# ui.net
KiCad netlist of a schematic drawn in Altium Designer
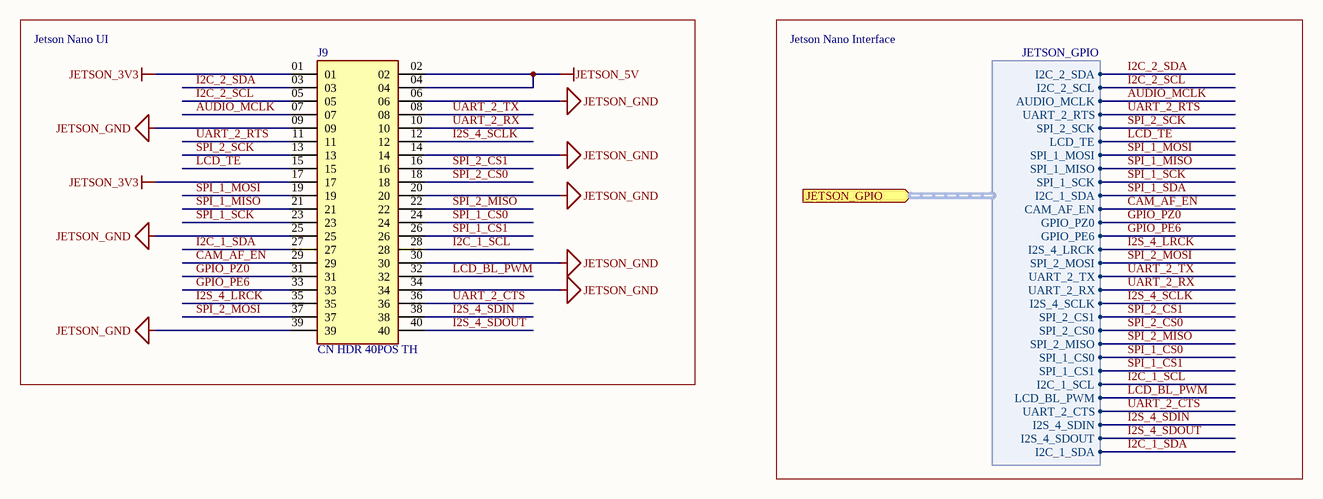
[diagram p0: ui.SchDoc]

(export (version "E")
  (design (tool "Eeschema 10.0.6"))
  (components
    (comp (ref "J9")
      (value "CN HDR 40POS TH")
      (footprint "SAMTEC_SSQ-120-22-G-D")
      (description "SSQ - Samtec 2.54mm Square Tail Dual Row Socket Strip 8.5mm Profile")
      (fields (field (name "MF") "Samtec") (field (name "MP") "SSQ-120-22-G-D"))
      (libsource (lib "AltiumLibraries") (part "CN HDR 40POS TH"))
    )
  )
  (nets
    (net (code "2") (name "/AUDIO_MCLK") (class "Default")
      (node (ref "J9") (pin "07") (pinfunction "07_07") (pintype "passive"))
    )
    (net (code "3") (name "/CAM_AF_EN") (class "Default")
      (node (ref "J9") (pin "29") (pinfunction "29_29") (pintype "passive"))
    )
    (net (code "4") (name "/GPIO_PE6") (class "Default")
      (node (ref "J9") (pin "33") (pinfunction "33_33") (pintype "passive"))
    )
    (net (code "5") (name "/GPIO_PZ0") (class "Default")
      (node (ref "J9") (pin "31") (pinfunction "31_31") (pintype "passive"))
    )
    (net (code "6") (name "/I2C_1_SCL") (class "Default")
      (node (ref "J9") (pin "28") (pinfunction "28_28") (pintype "passive"))
    )
    (net (code "7") (name "/I2C_1_SDA") (class "Default")
      (node (ref "J9") (pin "27") (pinfunction "27_27") (pintype "passive"))
    )
    (net (code "8") (name "/I2C_2_SCL") (class "Default")
      (node (ref "J9") (pin "05") (pinfunction "05_05") (pintype "passive"))
    )
    (net (code "9") (name "/I2C_2_SDA") (class "Default")
      (node (ref "J9") (pin "03") (pinfunction "03_03") (pintype "passive"))
    )
    (net (code "10") (name "/I2S_4_LRCK") (class "Default")
      (node (ref "J9") (pin "35") (pinfunction "35_35") (pintype "passive"))
    )
    (net (code "11") (name "/I2S_4_SCLK") (class "Default")
      (node (ref "J9") (pin "12") (pinfunction "12_12") (pintype "passive"))
    )
    (net (code "12") (name "/I2S_4_SDIN") (class "Default")
      (node (ref "J9") (pin "38") (pinfunction "38_38") (pintype "passive"))
    )
    (net (code "13") (name "/I2S_4_SDOUT") (class "Default")
      (node (ref "J9") (pin "40") (pinfunction "40_40") (pintype "passive"))
    )
    (net (code "14") (name "/LCD_BL_PWM") (class "Default")
      (node (ref "J9") (pin "32") (pinfunction "32_32") (pintype "passive"))
    )
    (net (code "15") (name "/LCD_TE") (class "Default")
      (node (ref "J9") (pin "15") (pinfunction "15_15") (pintype "passive"))
    )
    (net (code "16") (name "/SPI_1_CS0") (class "Default")
      (node (ref "J9") (pin "24") (pinfunction "24_24") (pintype "passive"))
    )
    (net (code "17") (name "/SPI_1_CS1") (class "Default")
      (node (ref "J9") (pin "26") (pinfunction "26_26") (pintype "passive"))
    )
    (net (code "18") (name "/SPI_1_MISO") (class "Default")
      (node (ref "J9") (pin "21") (pinfunction "21_21") (pintype "passive"))
    )
    (net (code "19") (name "/SPI_1_MOSI") (class "Default")
      (node (ref "J9") (pin "19") (pinfunction "19_19") (pintype "passive"))
    )
    (net (code "20") (name "/SPI_1_SCK") (class "Default")
      (node (ref "J9") (pin "23") (pinfunction "23_23") (pintype "passive"))
    )
    (net (code "22") (name "/SPI_2_CS0") (class "Default")
      (node (ref "J9") (pin "18") (pinfunction "18_18") (pintype "passive"))
    )
    (net (code "23") (name "/SPI_2_CS1") (class "Default")
      (node (ref "J9") (pin "16") (pinfunction "16_16") (pintype "passive"))
    )
    (net (code "24") (name "/SPI_2_MISO") (class "Default")
      (node (ref "J9") (pin "22") (pinfunction "22_22") (pintype "passive"))
    )
    (net (code "25") (name "/SPI_2_MOSI") (class "Default")
      (node (ref "J9") (pin "37") (pinfunction "37_37") (pintype "passive"))
    )
    (net (code "26") (name "/SPI_2_SCK") (class "Default")
      (node (ref "J9") (pin "13") (pinfunction "13_13") (pintype "passive"))
    )
    (net (code "27") (name "/UART_2_CTS") (class "Default")
      (node (ref "J9") (pin "36") (pinfunction "36_36") (pintype "passive"))
    )
    (net (code "28") (name "/UART_2_RTS") (class "Default")
      (node (ref "J9") (pin "11") (pinfunction "11_11") (pintype "passive"))
    )
    (net (code "29") (name "/UART_2_RX") (class "Default")
      (node (ref "J9") (pin "10") (pinfunction "10_10") (pintype "passive"))
    )
    (net (code "30") (name "/UART_2_TX") (class "Default")
      (node (ref "J9") (pin "08") (pinfunction "08_08") (pintype "passive"))
    )
    (net (code "32") (name "JETSON_3V3") (class "Default")
      (node (ref "J9") (pin "01") (pinfunction "01_01") (pintype "passive"))
      (node (ref "J9") (pin "17") (pinfunction "17_17") (pintype "passive"))
    )
    (net (code "33") (name "JETSON_5V") (class "Default")
      (node (ref "J9") (pin "02") (pinfunction "02_02") (pintype "passive"))
      (node (ref "J9") (pin "04") (pinfunction "04_04") (pintype "passive"))
    )
    (net (code "34") (name "JETSON_GND") (class "Default")
      (node (ref "J9") (pin "06") (pinfunction "06_06") (pintype "passive"))
      (node (ref "J9") (pin "09") (pinfunction "09_09") (pintype "passive"))
      (node (ref "J9") (pin "14") (pinfunction "14_14") (pintype "passive"))
      (node (ref "J9") (pin "20") (pinfunction "20_20") (pintype "passive"))
      (node (ref "J9") (pin "25") (pinfunction "25_25") (pintype "passive"))
      (node (ref "J9") (pin "30") (pinfunction "30_30") (pintype "passive"))
      (node (ref "J9") (pin "34") (pinfunction "34_34") (pintype "passive"))
      (node (ref "J9") (pin "39") (pinfunction "39_39") (pintype "passive"))
    )
  )
)
